# Sheet1.net
KiCad netlist of a schematic drawn in Altium Designer
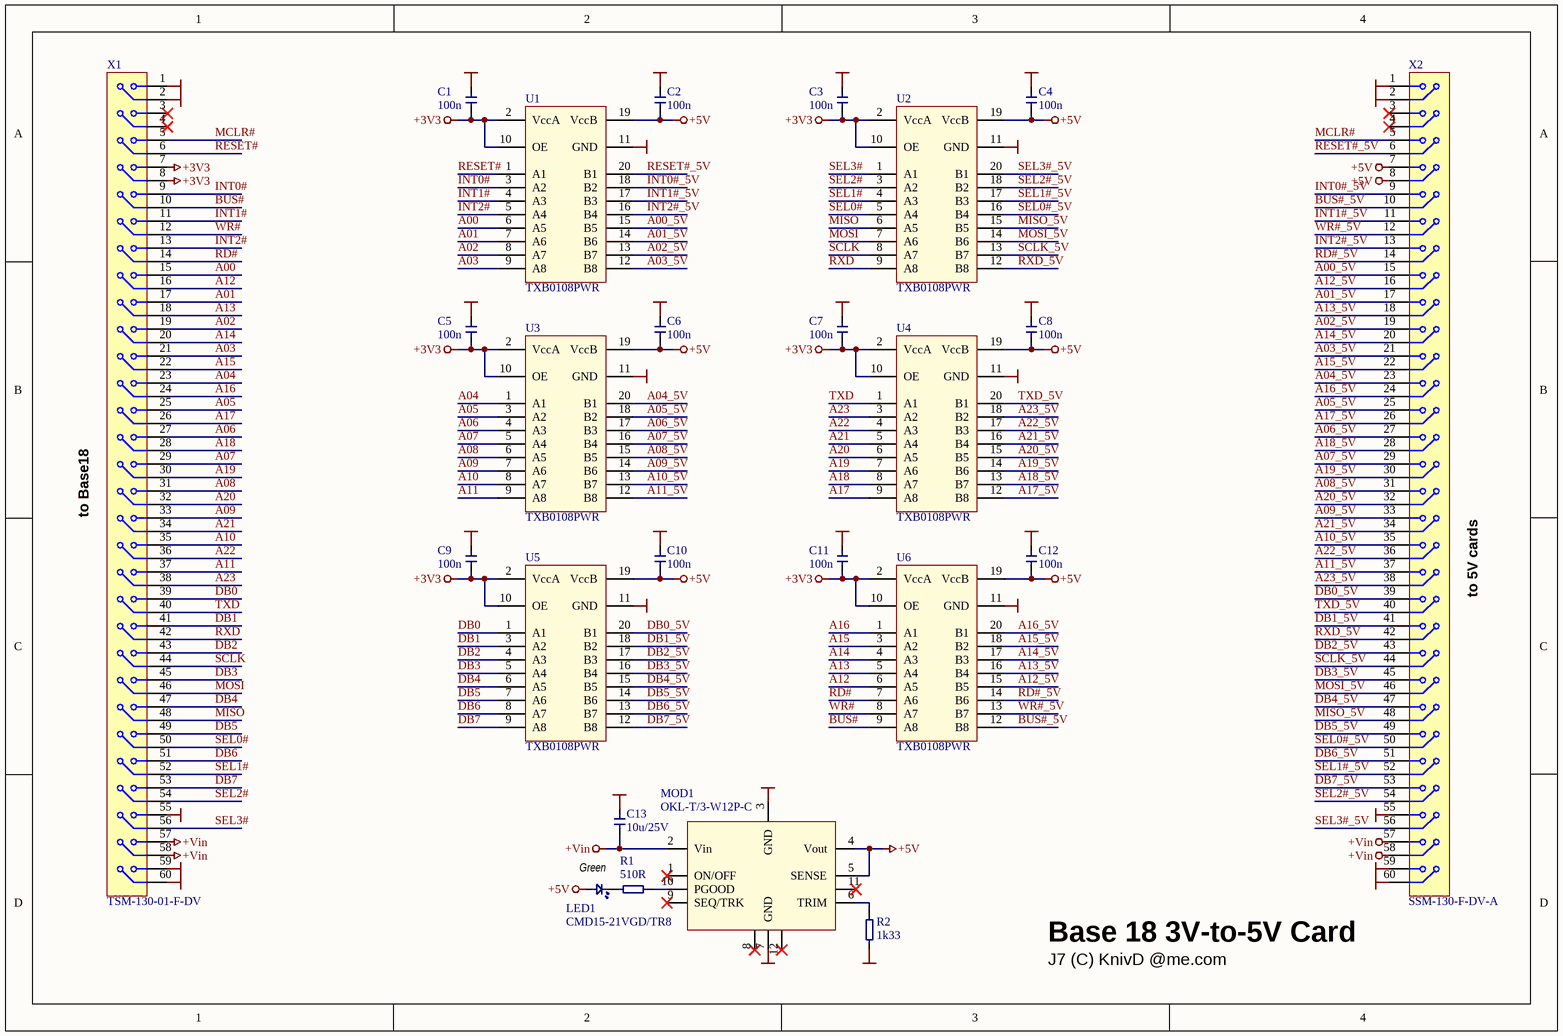
[diagram p0: Sheet1.SchDoc]

(export (version "E")
  (design (tool "Eeschema 10.0.6"))
  (components
    (comp (ref "C1")
      (value "100n")
      (footprint "CAPC3216X110N")
      (description "Capacitor")
      (libsource (lib "Discretes") (part "Capacitor"))
    )
    (comp (ref "C2")
      (value "100n")
      (footprint "CAPC3216X110N")
      (description "Capacitor")
      (libsource (lib "Discretes") (part "Capacitor"))
    )
    (comp (ref "C3")
      (value "100n")
      (footprint "CAPC3216X110N")
      (description "Capacitor")
      (libsource (lib "Discretes") (part "Capacitor"))
    )
    (comp (ref "C4")
      (value "100n")
      (footprint "CAPC3216X110N")
      (description "Capacitor")
      (libsource (lib "Discretes") (part "Capacitor"))
    )
    (comp (ref "C5")
      (value "100n")
      (footprint "CAPC3216X110N")
      (description "Capacitor")
      (libsource (lib "Discretes") (part "Capacitor"))
    )
    (comp (ref "C6")
      (value "100n")
      (footprint "CAPC3216X110N")
      (description "Capacitor")
      (libsource (lib "Discretes") (part "Capacitor"))
    )
    (comp (ref "C7")
      (value "100n")
      (footprint "CAPC3216X110N")
      (description "Capacitor")
      (libsource (lib "Discretes") (part "Capacitor"))
    )
    (comp (ref "C8")
      (value "100n")
      (footprint "CAPC3216X110N")
      (description "Capacitor")
      (libsource (lib "Discretes") (part "Capacitor"))
    )
    (comp (ref "C9")
      (value "100n")
      (footprint "CAPC3216X110N")
      (description "Capacitor")
      (libsource (lib "Discretes") (part "Capacitor"))
    )
    (comp (ref "C10")
      (value "100n")
      (footprint "CAPC3216X110N")
      (description "Capacitor")
      (libsource (lib "Discretes") (part "Capacitor"))
    )
    (comp (ref "C11")
      (value "100n")
      (footprint "CAPC3216X110N")
      (description "Capacitor")
      (libsource (lib "Discretes") (part "Capacitor"))
    )
    (comp (ref "C12")
      (value "100n")
      (footprint "CAPC3216X110N")
      (description "Capacitor")
      (libsource (lib "Discretes") (part "Capacitor"))
    )
    (comp (ref "C13")
      (value "10u/25V")
      (footprint "CAPC3216X110N")
      (description "Capacitor")
      (fields (field (name "NOTE") "10u/25V"))
      (libsource (lib "Discretes") (part "Capacitor"))
    )
    (comp (ref "LED1")
      (value "CMD15-21VGD/TR8")
      (footprint "LED_OSRAM_LGN971")
      (description "Light Emitting Diode")
      (libsource (lib "Discretes") (part "LED"))
    )
    (comp (ref "MOD1")
      (value "OKL-T/3-W12P-C")
      (footprint "OKL-T/3-W12")
      (description "Programmable Output 3-Amp iLGA SMT PoLs")
      (fields (field (name "MANUFACTURER") "Murata"))
      (libsource (lib "Modules") (part "OKL-T/3-W12"))
    )
    (comp (ref "R1")
      (value "510R")
      (footprint "RESC3216X75N")
      (description "Resistor")
      (libsource (lib "Discretes") (part "Resistor"))
    )
    (comp (ref "R2")
      (value "1k33")
      (footprint "RESC3216X75N")
      (description "Resistor")
      (libsource (lib "") (part "Resistor_1"))
    )
    (comp (ref "U1")
      (value "TXB0108PWR")
      (footprint "SOP65P640X120-20N")
      (description "8-bit bidirectional voltage translator")
      (fields (field (name "MANUFACTURER") "Texas Instruments"))
      (libsource (lib "IC Interface") (part "TXB0108PWR"))
    )
    (comp (ref "U2")
      (value "TXB0108PWR")
      (footprint "SOP65P640X120-20N")
      (description "8-bit bidirectional voltage translator")
      (fields (field (name "MANUFACTURER") "Texas Instruments"))
      (libsource (lib "IC Interface") (part "TXB0108PWR"))
    )
    (comp (ref "U3")
      (value "TXB0108PWR")
      (footprint "SOP65P640X120-20N")
      (description "8-bit bidirectional voltage translator")
      (fields (field (name "MANUFACTURER") "Texas Instruments"))
      (libsource (lib "IC Interface") (part "TXB0108PWR"))
    )
    (comp (ref "U4")
      (value "TXB0108PWR")
      (footprint "SOP65P640X120-20N")
      (description "8-bit bidirectional voltage translator")
      (fields (field (name "MANUFACTURER") "Texas Instruments"))
      (libsource (lib "IC Interface") (part "TXB0108PWR"))
    )
    (comp (ref "U5")
      (value "TXB0108PWR")
      (footprint "SOP65P640X120-20N")
      (description "8-bit bidirectional voltage translator")
      (fields (field (name "MANUFACTURER") "Texas Instruments"))
      (libsource (lib "IC Interface") (part "TXB0108PWR"))
    )
    (comp (ref "U6")
      (value "TXB0108PWR")
      (footprint "SOP65P640X120-20N")
      (description "8-bit bidirectional voltage translator")
      (fields (field (name "MANUFACTURER") "Texas Instruments"))
      (libsource (lib "IC Interface") (part "TXB0108PWR"))
    )
    (comp (ref "X1")
      (value "TSM-130-01-F-DV")
      (footprint "2015-2X30XD-M")
      (description "Dual row, 60-way connector")
      (libsource (lib "Connectors") (part "Connector 2x30"))
    )
    (comp (ref "X2")
      (value "SSM-130-F-DV-A")
      (footprint "2015-2X30XD-F")
      (description "Dual row, 60-way connector")
      (libsource (lib "Connectors") (part "Connector 2x30"))
    )
  )
  (nets
    (net (code "1") (name "+3V3") (class "Default")
      (node (ref "C1") (pin "1") (pintype "passive"))
      (node (ref "C11") (pin "1") (pintype "passive"))
      (node (ref "C3") (pin "1") (pintype "passive"))
      (node (ref "C5") (pin "1") (pintype "passive"))
      (node (ref "C7") (pin "1") (pintype "passive"))
      (node (ref "C9") (pin "1") (pintype "passive"))
      (node (ref "U1") (pin "10") (pinfunction "OE_10") (pintype "passive"))
      (node (ref "U1") (pin "2") (pinfunction "VccA_2") (pintype "passive"))
      (node (ref "U2") (pin "10") (pinfunction "OE_10") (pintype "passive"))
      (node (ref "U2") (pin "2") (pinfunction "VccA_2") (pintype "passive"))
      (node (ref "U3") (pin "10") (pinfunction "OE_10") (pintype "passive"))
      (node (ref "U3") (pin "2") (pinfunction "VccA_2") (pintype "passive"))
      (node (ref "U4") (pin "10") (pinfunction "OE_10") (pintype "passive"))
      (node (ref "U4") (pin "2") (pinfunction "VccA_2") (pintype "passive"))
      (node (ref "U5") (pin "10") (pinfunction "OE_10") (pintype "passive"))
      (node (ref "U5") (pin "2") (pinfunction "VccA_2") (pintype "passive"))
      (node (ref "U6") (pin "10") (pinfunction "OE_10") (pintype "passive"))
      (node (ref "U6") (pin "2") (pinfunction "VccA_2") (pintype "passive"))
      (node (ref "X1") (pin "7") (pinfunction "7_7") (pintype "passive"))
      (node (ref "X1") (pin "8") (pinfunction "8_8") (pintype "passive"))
    )
    (net (code "2") (name "+5V") (class "Default")
      (node (ref "C10") (pin "1") (pintype "passive"))
      (node (ref "C12") (pin "1") (pintype "passive"))
      (node (ref "C2") (pin "1") (pintype "passive"))
      (node (ref "C4") (pin "1") (pintype "passive"))
      (node (ref "C6") (pin "1") (pintype "passive"))
      (node (ref "C8") (pin "1") (pintype "passive"))
      (node (ref "LED1") (pin "2") (pintype "passive"))
      (node (ref "MOD1") (pin "4") (pinfunction "Vout_4") (pintype "passive"))
      (node (ref "MOD1") (pin "5") (pinfunction "SENSE_5") (pintype "passive"))
      (node (ref "U1") (pin "19") (pinfunction "VccB_19") (pintype "passive"))
      (node (ref "U2") (pin "19") (pinfunction "VccB_19") (pintype "passive"))
      (node (ref "U3") (pin "19") (pinfunction "VccB_19") (pintype "passive"))
      (node (ref "U4") (pin "19") (pinfunction "VccB_19") (pintype "passive"))
      (node (ref "U5") (pin "19") (pinfunction "VccB_19") (pintype "passive"))
      (node (ref "U6") (pin "19") (pinfunction "VccB_19") (pintype "passive"))
      (node (ref "X2") (pin "7") (pinfunction "7_7") (pintype "passive"))
      (node (ref "X2") (pin "8") (pinfunction "8_8") (pintype "passive"))
    )
    (net (code "3") (name "+Vin") (class "Default")
      (node (ref "C13") (pin "2") (pintype "passive"))
      (node (ref "MOD1") (pin "2") (pinfunction "Vin_2") (pintype "passive"))
      (node (ref "X1") (pin "57") (pinfunction "57_57") (pintype "passive"))
      (node (ref "X1") (pin "58") (pinfunction "58_58") (pintype "passive"))
      (node (ref "X2") (pin "57") (pinfunction "57_57") (pintype "passive"))
      (node (ref "X2") (pin "58") (pinfunction "58_58") (pintype "passive"))
    )
    (net (code "4") (name "/A00") (class "Default")
      (node (ref "U1") (pin "6") (pinfunction "A5_6") (pintype "passive"))
      (node (ref "X1") (pin "15") (pinfunction "15_15") (pintype "passive"))
    )
    (net (code "5") (name "/A00_5V") (class "Default")
      (node (ref "U1") (pin "15") (pinfunction "B5_15") (pintype "passive"))
      (node (ref "X2") (pin "15") (pinfunction "15_15") (pintype "passive"))
    )
    (net (code "6") (name "/A01") (class "Default")
      (node (ref "U1") (pin "7") (pinfunction "A6_7") (pintype "passive"))
      (node (ref "X1") (pin "17") (pinfunction "17_17") (pintype "passive"))
    )
    (net (code "7") (name "/A01_5V") (class "Default")
      (node (ref "U1") (pin "14") (pinfunction "B6_14") (pintype "passive"))
      (node (ref "X2") (pin "17") (pinfunction "17_17") (pintype "passive"))
    )
    (net (code "8") (name "/A02") (class "Default")
      (node (ref "U1") (pin "8") (pinfunction "A7_8") (pintype "passive"))
      (node (ref "X1") (pin "19") (pinfunction "19_19") (pintype "passive"))
    )
    (net (code "9") (name "/A02_5V") (class "Default")
      (node (ref "U1") (pin "13") (pinfunction "B7_13") (pintype "passive"))
      (node (ref "X2") (pin "19") (pinfunction "19_19") (pintype "passive"))
    )
    (net (code "10") (name "/A03") (class "Default")
      (node (ref "U1") (pin "9") (pinfunction "A8_9") (pintype "passive"))
      (node (ref "X1") (pin "21") (pinfunction "21_21") (pintype "passive"))
    )
    (net (code "11") (name "/A03_5V") (class "Default")
      (node (ref "U1") (pin "12") (pinfunction "B8_12") (pintype "passive"))
      (node (ref "X2") (pin "21") (pinfunction "21_21") (pintype "passive"))
    )
    (net (code "12") (name "/A04") (class "Default")
      (node (ref "U3") (pin "1") (pinfunction "A1_1") (pintype "passive"))
      (node (ref "X1") (pin "23") (pinfunction "23_23") (pintype "passive"))
    )
    (net (code "13") (name "/A04_5V") (class "Default")
      (node (ref "U3") (pin "20") (pinfunction "B1_20") (pintype "passive"))
      (node (ref "X2") (pin "23") (pinfunction "23_23") (pintype "passive"))
    )
    (net (code "14") (name "/A05") (class "Default")
      (node (ref "U3") (pin "3") (pinfunction "A2_3") (pintype "passive"))
      (node (ref "X1") (pin "25") (pinfunction "25_25") (pintype "passive"))
    )
    (net (code "15") (name "/A05_5V") (class "Default")
      (node (ref "U3") (pin "18") (pinfunction "B2_18") (pintype "passive"))
      (node (ref "X2") (pin "25") (pinfunction "25_25") (pintype "passive"))
    )
    (net (code "16") (name "/A06") (class "Default")
      (node (ref "U3") (pin "4") (pinfunction "A3_4") (pintype "passive"))
      (node (ref "X1") (pin "27") (pinfunction "27_27") (pintype "passive"))
    )
    (net (code "17") (name "/A06_5V") (class "Default")
      (node (ref "U3") (pin "17") (pinfunction "B3_17") (pintype "passive"))
      (node (ref "X2") (pin "27") (pinfunction "27_27") (pintype "passive"))
    )
    (net (code "18") (name "/A07") (class "Default")
      (node (ref "U3") (pin "5") (pinfunction "A4_5") (pintype "passive"))
      (node (ref "X1") (pin "29") (pinfunction "29_29") (pintype "passive"))
    )
    (net (code "19") (name "/A07_5V") (class "Default")
      (node (ref "U3") (pin "16") (pinfunction "B4_16") (pintype "passive"))
      (node (ref "X2") (pin "29") (pinfunction "29_29") (pintype "passive"))
    )
    (net (code "20") (name "/A08") (class "Default")
      (node (ref "U3") (pin "6") (pinfunction "A5_6") (pintype "passive"))
      (node (ref "X1") (pin "31") (pinfunction "31_31") (pintype "passive"))
    )
    (net (code "21") (name "/A08_5V") (class "Default")
      (node (ref "U3") (pin "15") (pinfunction "B5_15") (pintype "passive"))
      (node (ref "X2") (pin "31") (pinfunction "31_31") (pintype "passive"))
    )
    (net (code "22") (name "/A09") (class "Default")
      (node (ref "U3") (pin "7") (pinfunction "A6_7") (pintype "passive"))
      (node (ref "X1") (pin "33") (pinfunction "33_33") (pintype "passive"))
    )
    (net (code "23") (name "/A09_5V") (class "Default")
      (node (ref "U3") (pin "14") (pinfunction "B6_14") (pintype "passive"))
      (node (ref "X2") (pin "33") (pinfunction "33_33") (pintype "passive"))
    )
    (net (code "24") (name "/A10") (class "Default")
      (node (ref "U3") (pin "8") (pinfunction "A7_8") (pintype "passive"))
      (node (ref "X1") (pin "35") (pinfunction "35_35") (pintype "passive"))
    )
    (net (code "25") (name "/A10_5V") (class "Default")
      (node (ref "U3") (pin "13") (pinfunction "B7_13") (pintype "passive"))
      (node (ref "X2") (pin "35") (pinfunction "35_35") (pintype "passive"))
    )
    (net (code "26") (name "/A11") (class "Default")
      (node (ref "U3") (pin "9") (pinfunction "A8_9") (pintype "passive"))
      (node (ref "X1") (pin "37") (pinfunction "37_37") (pintype "passive"))
    )
    (net (code "27") (name "/A11_5V") (class "Default")
      (node (ref "U3") (pin "12") (pinfunction "B8_12") (pintype "passive"))
      (node (ref "X2") (pin "37") (pinfunction "37_37") (pintype "passive"))
    )
    (net (code "28") (name "/A12") (class "Default")
      (node (ref "U6") (pin "6") (pinfunction "A5_6") (pintype "passive"))
      (node (ref "X1") (pin "16") (pinfunction "16_16") (pintype "passive"))
    )
    (net (code "29") (name "/A12_5V") (class "Default")
      (node (ref "U6") (pin "15") (pinfunction "B5_15") (pintype "passive"))
      (node (ref "X2") (pin "16") (pinfunction "16_16") (pintype "passive"))
    )
    (net (code "30") (name "/A13") (class "Default")
      (node (ref "U6") (pin "5") (pinfunction "A4_5") (pintype "passive"))
      (node (ref "X1") (pin "18") (pinfunction "18_18") (pintype "passive"))
    )
    (net (code "31") (name "/A13_5V") (class "Default")
      (node (ref "U6") (pin "16") (pinfunction "B4_16") (pintype "passive"))
      (node (ref "X2") (pin "18") (pinfunction "18_18") (pintype "passive"))
    )
    (net (code "32") (name "/A14") (class "Default")
      (node (ref "U6") (pin "4") (pinfunction "A3_4") (pintype "passive"))
      (node (ref "X1") (pin "20") (pinfunction "20_20") (pintype "passive"))
    )
    (net (code "33") (name "/A14_5V") (class "Default")
      (node (ref "U6") (pin "17") (pinfunction "B3_17") (pintype "passive"))
      (node (ref "X2") (pin "20") (pinfunction "20_20") (pintype "passive"))
    )
    (net (code "34") (name "/A15") (class "Default")
      (node (ref "U6") (pin "3") (pinfunction "A2_3") (pintype "passive"))
      (node (ref "X1") (pin "22") (pinfunction "22_22") (pintype "passive"))
    )
    (net (code "35") (name "/A15_5V") (class "Default")
      (node (ref "U6") (pin "18") (pinfunction "B2_18") (pintype "passive"))
      (node (ref "X2") (pin "22") (pinfunction "22_22") (pintype "passive"))
    )
    (net (code "36") (name "/A16") (class "Default")
      (node (ref "U6") (pin "1") (pinfunction "A1_1") (pintype "passive"))
      (node (ref "X1") (pin "24") (pinfunction "24_24") (pintype "passive"))
    )
    (net (code "37") (name "/A16_5V") (class "Default")
      (node (ref "U6") (pin "20") (pinfunction "B1_20") (pintype "passive"))
      (node (ref "X2") (pin "24") (pinfunction "24_24") (pintype "passive"))
    )
    (net (code "38") (name "/A17") (class "Default")
      (node (ref "U4") (pin "9") (pinfunction "A8_9") (pintype "passive"))
      (node (ref "X1") (pin "26") (pinfunction "26_26") (pintype "passive"))
    )
    (net (code "39") (name "/A17_5V") (class "Default")
      (node (ref "U4") (pin "12") (pinfunction "B8_12") (pintype "passive"))
      (node (ref "X2") (pin "26") (pinfunction "26_26") (pintype "passive"))
    )
    (net (code "40") (name "/A18") (class "Default")
      (node (ref "U4") (pin "8") (pinfunction "A7_8") (pintype "passive"))
      (node (ref "X1") (pin "28") (pinfunction "28_28") (pintype "passive"))
    )
    (net (code "41") (name "/A18_5V") (class "Default")
      (node (ref "U4") (pin "13") (pinfunction "B7_13") (pintype "passive"))
      (node (ref "X2") (pin "28") (pinfunction "28_28") (pintype "passive"))
    )
    (net (code "42") (name "/A19") (class "Default")
      (node (ref "U4") (pin "7") (pinfunction "A6_7") (pintype "passive"))
      (node (ref "X1") (pin "30") (pinfunction "30_30") (pintype "passive"))
    )
    (net (code "43") (name "/A19_5V") (class "Default")
      (node (ref "U4") (pin "14") (pinfunction "B6_14") (pintype "passive"))
      (node (ref "X2") (pin "30") (pinfunction "30_30") (pintype "passive"))
    )
    (net (code "44") (name "/A20") (class "Default")
      (node (ref "U4") (pin "6") (pinfunction "A5_6") (pintype "passive"))
      (node (ref "X1") (pin "32") (pinfunction "32_32") (pintype "passive"))
    )
    (net (code "45") (name "/A20_5V") (class "Default")
      (node (ref "U4") (pin "15") (pinfunction "B5_15") (pintype "passive"))
      (node (ref "X2") (pin "32") (pinfunction "32_32") (pintype "passive"))
    )
    (net (code "46") (name "/A21") (class "Default")
      (node (ref "U4") (pin "5") (pinfunction "A4_5") (pintype "passive"))
      (node (ref "X1") (pin "34") (pinfunction "34_34") (pintype "passive"))
    )
    (net (code "47") (name "/A21_5V") (class "Default")
      (node (ref "U4") (pin "16") (pinfunction "B4_16") (pintype "passive"))
      (node (ref "X2") (pin "34") (pinfunction "34_34") (pintype "passive"))
    )
    (net (code "48") (name "/A22") (class "Default")
      (node (ref "U4") (pin "4") (pinfunction "A3_4") (pintype "passive"))
      (node (ref "X1") (pin "36") (pinfunction "36_36") (pintype "passive"))
    )
    (net (code "49") (name "/A22_5V") (class "Default")
      (node (ref "U4") (pin "17") (pinfunction "B3_17") (pintype "passive"))
      (node (ref "X2") (pin "36") (pinfunction "36_36") (pintype "passive"))
    )
    (net (code "50") (name "/A23") (class "Default")
      (node (ref "U4") (pin "3") (pinfunction "A2_3") (pintype "passive"))
      (node (ref "X1") (pin "38") (pinfunction "38_38") (pintype "passive"))
    )
    (net (code "51") (name "/A23_5V") (class "Default")
      (node (ref "U4") (pin "18") (pinfunction "B2_18") (pintype "passive"))
      (node (ref "X2") (pin "38") (pinfunction "38_38") (pintype "passive"))
    )
    (net (code "52") (name "/BUS#") (class "Default")
      (node (ref "U6") (pin "9") (pinfunction "A8_9") (pintype "passive"))
      (node (ref "X1") (pin "10") (pinfunction "10_10") (pintype "passive"))
    )
    (net (code "53") (name "/BUS#_5V") (class "Default")
      (node (ref "U6") (pin "12") (pinfunction "B8_12") (pintype "passive"))
      (node (ref "X2") (pin "10") (pinfunction "10_10") (pintype "passive"))
    )
    (net (code "54") (name "/DB0") (class "Default")
      (node (ref "U5") (pin "1") (pinfunction "A1_1") (pintype "passive"))
      (node (ref "X1") (pin "39") (pinfunction "39_39") (pintype "passive"))
    )
    (net (code "55") (name "/DB0_5V") (class "Default")
      (node (ref "U5") (pin "20") (pinfunction "B1_20") (pintype "passive"))
      (node (ref "X2") (pin "39") (pinfunction "39_39") (pintype "passive"))
    )
    (net (code "56") (name "/DB1") (class "Default")
      (node (ref "U5") (pin "3") (pinfunction "A2_3") (pintype "passive"))
      (node (ref "X1") (pin "41") (pinfunction "41_41") (pintype "passive"))
    )
    (net (code "57") (name "/DB1_5V") (class "Default")
      (node (ref "U5") (pin "18") (pinfunction "B2_18") (pintype "passive"))
      (node (ref "X2") (pin "41") (pinfunction "41_41") (pintype "passive"))
    )
    (net (code "58") (name "/DB2") (class "Default")
      (node (ref "U5") (pin "4") (pinfunction "A3_4") (pintype "passive"))
      (node (ref "X1") (pin "43") (pinfunction "43_43") (pintype "passive"))
    )
    (net (code "59") (name "/DB2_5V") (class "Default")
      (node (ref "U5") (pin "17") (pinfunction "B3_17") (pintype "passive"))
      (node (ref "X2") (pin "43") (pinfunction "43_43") (pintype "passive"))
    )
    (net (code "60") (name "/DB3") (class "Default")
      (node (ref "U5") (pin "5") (pinfunction "A4_5") (pintype "passive"))
      (node (ref "X1") (pin "45") (pinfunction "45_45") (pintype "passive"))
    )
    (net (code "61") (name "/DB3_5V") (class "Default")
      (node (ref "U5") (pin "16") (pinfunction "B4_16") (pintype "passive"))
      (node (ref "X2") (pin "45") (pinfunction "45_45") (pintype "passive"))
    )
    (net (code "62") (name "/DB4") (class "Default")
      (node (ref "U5") (pin "6") (pinfunction "A5_6") (pintype "passive"))
      (node (ref "X1") (pin "47") (pinfunction "47_47") (pintype "passive"))
    )
    (net (code "63") (name "/DB4_5V") (class "Default")
      (node (ref "U5") (pin "15") (pinfunction "B5_15") (pintype "passive"))
      (node (ref "X2") (pin "47") (pinfunction "47_47") (pintype "passive"))
    )
    (net (code "64") (name "/DB5") (class "Default")
      (node (ref "U5") (pin "7") (pinfunction "A6_7") (pintype "passive"))
      (node (ref "X1") (pin "49") (pinfunction "49_49") (pintype "passive"))
    )
    (net (code "65") (name "/DB5_5V") (class "Default")
      (node (ref "U5") (pin "14") (pinfunction "B6_14") (pintype "passive"))
      (node (ref "X2") (pin "49") (pinfunction "49_49") (pintype "passive"))
    )
    (net (code "66") (name "/DB6") (class "Default")
      (node (ref "U5") (pin "8") (pinfunction "A7_8") (pintype "passive"))
      (node (ref "X1") (pin "51") (pinfunction "51_51") (pintype "passive"))
    )
    (net (code "67") (name "/DB6_5V") (class "Default")
      (node (ref "U5") (pin "13") (pinfunction "B7_13") (pintype "passive"))
      (node (ref "X2") (pin "51") (pinfunction "51_51") (pintype "passive"))
    )
    (net (code "68") (name "/DB7") (class "Default")
      (node (ref "U5") (pin "9") (pinfunction "A8_9") (pintype "passive"))
      (node (ref "X1") (pin "53") (pinfunction "53_53") (pintype "passive"))
    )
    (net (code "69") (name "/DB7_5V") (class "Default")
      (node (ref "U5") (pin "12") (pinfunction "B8_12") (pintype "passive"))
      (node (ref "X2") (pin "53") (pinfunction "53_53") (pintype "passive"))
    )
    (net (code "70") (name "/INT0#") (class "Default")
      (node (ref "U1") (pin "3") (pinfunction "A2_3") (pintype "passive"))
      (node (ref "X1") (pin "9") (pinfunction "9_9") (pintype "passive"))
    )
    (net (code "71") (name "/INT0#_5V") (class "Default")
      (node (ref "U1") (pin "18") (pinfunction "B2_18") (pintype "passive"))
      (node (ref "X2") (pin "9") (pinfunction "9_9") (pintype "passive"))
    )
    (net (code "72") (name "/INT1#") (class "Default")
      (node (ref "U1") (pin "4") (pinfunction "A3_4") (pintype "passive"))
      (node (ref "X1") (pin "11") (pinfunction "11_11") (pintype "passive"))
    )
    (net (code "73") (name "/INT1#_5V") (class "Default")
      (node (ref "U1") (pin "17") (pinfunction "B3_17") (pintype "passive"))
      (node (ref "X2") (pin "11") (pinfunction "11_11") (pintype "passive"))
    )
    (net (code "74") (name "/INT2#") (class "Default")
      (node (ref "U1") (pin "5") (pinfunction "A4_5") (pintype "passive"))
      (node (ref "X1") (pin "13") (pinfunction "13_13") (pintype "passive"))
    )
    (net (code "75") (name "/INT2#_5V") (class "Default")
      (node (ref "U1") (pin "16") (pinfunction "B4_16") (pintype "passive"))
      (node (ref "X2") (pin "13") (pinfunction "13_13") (pintype "passive"))
    )
    (net (code "76") (name "/MCLR#") (class "Default")
      (node (ref "X1") (pin "5") (pinfunction "5_5") (pintype "passive"))
      (node (ref "X2") (pin "5") (pinfunction "5_5") (pintype "passive"))
    )
    (net (code "77") (name "/MISO") (class "Default")
      (node (ref "U2") (pin "6") (pinfunction "A5_6") (pintype "passive"))
      (node (ref "X1") (pin "48") (pinfunction "48_48") (pintype "passive"))
    )
    (net (code "78") (name "/MISO_5V") (class "Default")
      (node (ref "U2") (pin "15") (pinfunction "B5_15") (pintype "passive"))
      (node (ref "X2") (pin "48") (pinfunction "48_48") (pintype "passive"))
    )
    (net (code "79") (name "/MOSI") (class "Default")
      (node (ref "U2") (pin "7") (pinfunction "A6_7") (pintype "passive"))
      (node (ref "X1") (pin "46") (pinfunction "46_46") (pintype "passive"))
    )
    (net (code "80") (name "/MOSI_5V") (class "Default")
      (node (ref "U2") (pin "14") (pinfunction "B6_14") (pintype "passive"))
      (node (ref "X2") (pin "46") (pinfunction "46_46") (pintype "passive"))
    )
    (net (code "81") (name "/RD#") (class "Default")
      (node (ref "U6") (pin "7") (pinfunction "A6_7") (pintype "passive"))
      (node (ref "X1") (pin "14") (pinfunction "14_14") (pintype "passive"))
    )
    (net (code "82") (name "/RD#_5V") (class "Default")
      (node (ref "U6") (pin "14") (pinfunction "B6_14") (pintype "passive"))
      (node (ref "X2") (pin "14") (pinfunction "14_14") (pintype "passive"))
    )
    (net (code "83") (name "/RESET#") (class "Default")
      (node (ref "U1") (pin "1") (pinfunction "A1_1") (pintype "passive"))
      (node (ref "X1") (pin "6") (pinfunction "6_6") (pintype "passive"))
    )
    (net (code "84") (name "/RESET#_5V") (class "Default")
      (node (ref "U1") (pin "20") (pinfunction "B1_20") (pintype "passive"))
      (node (ref "X2") (pin "6") (pinfunction "6_6") (pintype "passive"))
    )
    (net (code "85") (name "/RXD") (class "Default")
      (node (ref "U2") (pin "9") (pinfunction "A8_9") (pintype "passive"))
      (node (ref "X1") (pin "42") (pinfunction "42_42") (pintype "passive"))
    )
    (net (code "86") (name "/RXD_5V") (class "Default")
      (node (ref "U2") (pin "12") (pinfunction "B8_12") (pintype "passive"))
      (node (ref "X2") (pin "42") (pinfunction "42_42") (pintype "passive"))
    )
    (net (code "87") (name "/SCLK") (class "Default")
      (node (ref "U2") (pin "8") (pinfunction "A7_8") (pintype "passive"))
      (node (ref "X1") (pin "44") (pinfunction "44_44") (pintype "passive"))
    )
    (net (code "88") (name "/SCLK_5V") (class "Default")
      (node (ref "U2") (pin "13") (pinfunction "B7_13") (pintype "passive"))
      (node (ref "X2") (pin "44") (pinfunction "44_44") (pintype "passive"))
    )
    (net (code "89") (name "/SEL0#") (class "Default")
      (node (ref "U2") (pin "5") (pinfunction "A4_5") (pintype "passive"))
      (node (ref "X1") (pin "50") (pinfunction "50_50") (pintype "passive"))
    )
    (net (code "90") (name "/SEL0#_5V") (class "Default")
      (node (ref "U2") (pin "16") (pinfunction "B4_16") (pintype "passive"))
      (node (ref "X2") (pin "50") (pinfunction "50_50") (pintype "passive"))
    )
    (net (code "91") (name "/SEL1#") (class "Default")
      (node (ref "U2") (pin "4") (pinfunction "A3_4") (pintype "passive"))
      (node (ref "X1") (pin "52") (pinfunction "52_52") (pintype "passive"))
    )
    (net (code "92") (name "/SEL1#_5V") (class "Default")
      (node (ref "U2") (pin "17") (pinfunction "B3_17") (pintype "passive"))
      (node (ref "X2") (pin "52") (pinfunction "52_52") (pintype "passive"))
    )
    (net (code "93") (name "/SEL2#") (class "Default")
      (node (ref "U2") (pin "3") (pinfunction "A2_3") (pintype "passive"))
      (node (ref "X1") (pin "54") (pinfunction "54_54") (pintype "passive"))
    )
    (net (code "94") (name "/SEL2#_5V") (class "Default")
      (node (ref "U2") (pin "18") (pinfunction "B2_18") (pintype "passive"))
      (node (ref "X2") (pin "54") (pinfunction "54_54") (pintype "passive"))
    )
    (net (code "95") (name "/SEL3#") (class "Default")
      (node (ref "U2") (pin "1") (pinfunction "A1_1") (pintype "passive"))
      (node (ref "X1") (pin "56") (pinfunction "56_56") (pintype "passive"))
    )
    (net (code "96") (name "/SEL3#_5V") (class "Default")
      (node (ref "U2") (pin "20") (pinfunction "B1_20") (pintype "passive"))
      (node (ref "X2") (pin "56") (pinfunction "56_56") (pintype "passive"))
    )
    (net (code "97") (name "/TXD") (class "Default")
      (node (ref "U4") (pin "1") (pinfunction "A1_1") (pintype "passive"))
      (node (ref "X1") (pin "40") (pinfunction "40_40") (pintype "passive"))
    )
    (net (code "98") (name "/TXD_5V") (class "Default")
      (node (ref "U4") (pin "20") (pinfunction "B1_20") (pintype "passive"))
      (node (ref "X2") (pin "40") (pinfunction "40_40") (pintype "passive"))
    )
    (net (code "99") (name "/WR#") (class "Default")
      (node (ref "U6") (pin "8") (pinfunction "A7_8") (pintype "passive"))
      (node (ref "X1") (pin "12") (pinfunction "12_12") (pintype "passive"))
    )
    (net (code "100") (name "/WR#_5V") (class "Default")
      (node (ref "U6") (pin "13") (pinfunction "B7_13") (pintype "passive"))
      (node (ref "X2") (pin "12") (pinfunction "12_12") (pintype "passive"))
    )
    (net (code "101") (name "GND") (class "Default")
      (node (ref "C1") (pin "2") (pintype "passive"))
      (node (ref "C10") (pin "2") (pintype "passive"))
      (node (ref "C11") (pin "2") (pintype "passive"))
      (node (ref "C12") (pin "2") (pintype "passive"))
      (node (ref "C13") (pin "1") (pintype "passive"))
      (node (ref "C2") (pin "2") (pintype "passive"))
      (node (ref "C3") (pin "2") (pintype "passive"))
      (node (ref "C4") (pin "2") (pintype "passive"))
      (node (ref "C5") (pin "2") (pintype "passive"))
      (node (ref "C6") (pin "2") (pintype "passive"))
      (node (ref "C7") (pin "2") (pintype "passive"))
      (node (ref "C8") (pin "2") (pintype "passive"))
      (node (ref "C9") (pin "2") (pintype "passive"))
      (node (ref "MOD1") (pin "3") (pinfunction "GND_3") (pintype "passive"))
      (node (ref "MOD1") (pin "7") (pinfunction "GND_7") (pintype "passive"))
      (node (ref "R2") (pin "1") (pintype "passive"))
      (node (ref "U1") (pin "11") (pinfunction "GND_11") (pintype "passive"))
      (node (ref "U2") (pin "11") (pinfunction "GND_11") (pintype "passive"))
      (node (ref "U3") (pin "11") (pinfunction "GND_11") (pintype "passive"))
      (node (ref "U4") (pin "11") (pinfunction "GND_11") (pintype "passive"))
      (node (ref "U5") (pin "11") (pinfunction "GND_11") (pintype "passive"))
      (node (ref "U6") (pin "11") (pinfunction "GND_11") (pintype "passive"))
      (node (ref "X1") (pin "1") (pinfunction "1_1") (pintype "passive"))
      (node (ref "X1") (pin "2") (pinfunction "2_2") (pintype "passive"))
      (node (ref "X1") (pin "55") (pinfunction "55_55") (pintype "passive"))
      (node (ref "X1") (pin "59") (pinfunction "59_59") (pintype "passive"))
      (node (ref "X1") (pin "60") (pinfunction "60_60") (pintype "passive"))
      (node (ref "X2") (pin "1") (pinfunction "1_1") (pintype "passive"))
      (node (ref "X2") (pin "2") (pinfunction "2_2") (pintype "passive"))
      (node (ref "X2") (pin "55") (pinfunction "55_55") (pintype "passive"))
      (node (ref "X2") (pin "59") (pinfunction "59_59") (pintype "passive"))
      (node (ref "X2") (pin "60") (pinfunction "60_60") (pintype "passive"))
    )
    (net (code "102") (name "Net-(LED1-Pad1)") (class "Default")
      (node (ref "LED1") (pin "1") (pintype "passive"))
      (node (ref "R1") (pin "2") (pintype "passive"))
    )
    (net (code "103") (name "Net-(MOD1-PGOOD)") (class "Default")
      (node (ref "MOD1") (pin "10") (pinfunction "PGOOD_10") (pintype "passive"))
      (node (ref "R1") (pin "1") (pintype "passive"))
    )
    (net (code "104") (name "Net-(MOD1-TRIM)") (class "Default")
      (node (ref "MOD1") (pin "6") (pinfunction "TRIM_6") (pintype "passive"))
      (node (ref "R2") (pin "2") (pintype "passive"))
    )
    (net (code "105") (name "unconnected-(MOD1-ON{slash}OFF-Pad1)") (class "Default")
      (node (ref "MOD1") (pin "1") (pinfunction "ON/OFF_1") (pintype "passive+no_connect"))
    )
    (net (code "106") (name "unconnected-(MOD1-Pad8)") (class "Default")
      (node (ref "MOD1") (pin "8") (pintype "passive+no_connect"))
    )
    (net (code "107") (name "unconnected-(MOD1-Pad11)") (class "Default")
      (node (ref "MOD1") (pin "11") (pintype "passive+no_connect"))
    )
    (net (code "108") (name "unconnected-(MOD1-Pad12)") (class "Default")
      (node (ref "MOD1") (pin "12") (pintype "passive+no_connect"))
    )
    (net (code "109") (name "unconnected-(MOD1-SEQ{slash}TRK-Pad9)") (class "Default")
      (node (ref "MOD1") (pin "9") (pinfunction "SEQ/TRK_9") (pintype "passive+no_connect"))
    )
    (net (code "110") (name "unconnected-(X1-Pad3)") (class "Default")
      (node (ref "X1") (pin "3") (pinfunction "3_3") (pintype "passive+no_connect"))
    )
    (net (code "111") (name "unconnected-(X1-Pad4)") (class "Default")
      (node (ref "X1") (pin "4") (pinfunction "4_4") (pintype "passive+no_connect"))
    )
    (net (code "112") (name "unconnected-(X2-Pad3)") (class "Default")
      (node (ref "X2") (pin "3") (pinfunction "3_3") (pintype "passive+no_connect"))
    )
    (net (code "113") (name "unconnected-(X2-Pad4)") (class "Default")
      (node (ref "X2") (pin "4") (pinfunction "4_4") (pintype "passive+no_connect"))
    )
  )
)
